# SparkFun_Qwiic_Audio_Amp.net
KiCad netlist of a schematic drawn in EAGLE
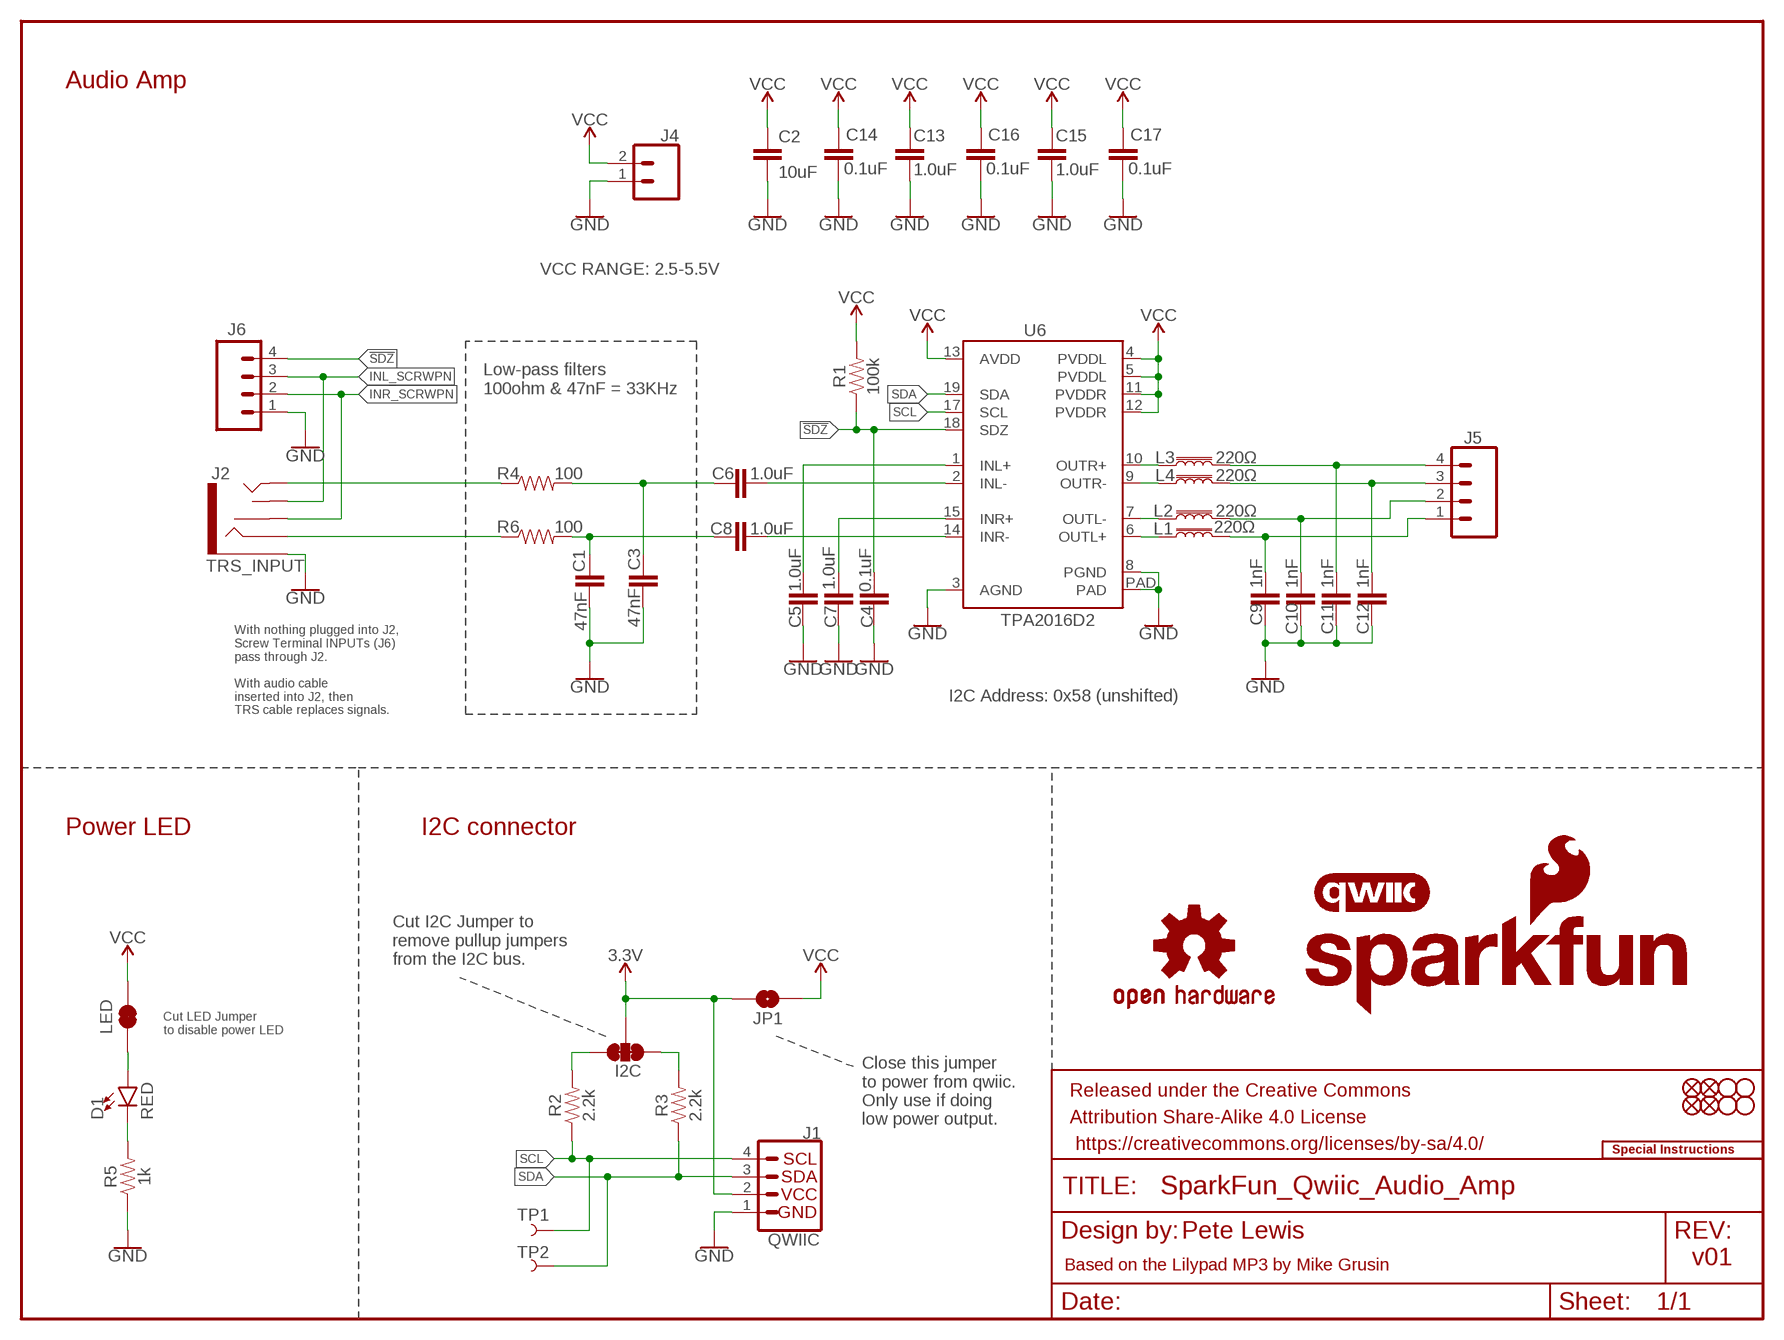
[diagram p0: schematic, sheet 1]

(export (version "E")
  (design (tool "Eeschema 10.0.6"))
  (components
    (comp (ref "C1")
      (value "47nF")
      (footprint "eagle-import:0402-TIGHT")
      (libsource (lib "eagle-import") (part "47NF-0402_TIGHT-25V-10%-X7R"))
    )
    (comp (ref "C2")
      (value "10uF")
      (footprint "eagle-import:0805")
      (libsource (lib "eagle-import") (part "10UF-0805-25V-10%"))
    )
    (comp (ref "C3")
      (value "47nF")
      (footprint "eagle-import:0402-TIGHT")
      (libsource (lib "eagle-import") (part "47NF-0402_TIGHT-25V-10%-X7R"))
    )
    (comp (ref "C4")
      (value "0.1uF")
      (footprint "eagle-import:0402-TIGHT")
      (libsource (lib "eagle-import") (part "0.1UF-0402T-16V-10%-X7R-WE"))
    )
    (comp (ref "C5")
      (value "1.0uF")
      (footprint "eagle-import:0402-TIGHT")
      (libsource (lib "eagle-import") (part "1.0UF-0402T-16V-10%"))
    )
    (comp (ref "C6")
      (value "1.0uF")
      (footprint "eagle-import:0402-TIGHT")
      (libsource (lib "eagle-import") (part "1.0UF-0402T-16V-10%"))
    )
    (comp (ref "C7")
      (value "1.0uF")
      (footprint "eagle-import:0402-TIGHT")
      (libsource (lib "eagle-import") (part "1.0UF-0402T-16V-10%"))
    )
    (comp (ref "C8")
      (value "1.0uF")
      (footprint "eagle-import:0402-TIGHT")
      (libsource (lib "eagle-import") (part "1.0UF-0402T-16V-10%"))
    )
    (comp (ref "C9")
      (value "1nF")
      (footprint "eagle-import:0402")
      (libsource (lib "eagle-import") (part "1.0NF/1000PF-0402-25V-10%-X7R"))
    )
    (comp (ref "C10")
      (value "1nF")
      (footprint "eagle-import:0402")
      (libsource (lib "eagle-import") (part "1.0NF/1000PF-0402-25V-10%-X7R"))
    )
    (comp (ref "C11")
      (value "1nF")
      (footprint "eagle-import:0402")
      (libsource (lib "eagle-import") (part "1.0NF/1000PF-0402-25V-10%-X7R"))
    )
    (comp (ref "C12")
      (value "1nF")
      (footprint "eagle-import:0402")
      (libsource (lib "eagle-import") (part "1.0NF/1000PF-0402-25V-10%-X7R"))
    )
    (comp (ref "C13")
      (value "1.0uF")
      (footprint "eagle-import:0402-TIGHT")
      (libsource (lib "eagle-import") (part "1.0UF-0402T-16V-10%"))
    )
    (comp (ref "C14")
      (value "0.1uF")
      (footprint "eagle-import:0402-TIGHT")
      (libsource (lib "eagle-import") (part "0.1UF-0402T-16V-10%-X7R-WE"))
    )
    (comp (ref "C15")
      (value "1.0uF")
      (footprint "eagle-import:0402-TIGHT")
      (libsource (lib "eagle-import") (part "1.0UF-0402T-16V-10%"))
    )
    (comp (ref "C16")
      (value "0.1uF")
      (footprint "eagle-import:0402-TIGHT")
      (libsource (lib "eagle-import") (part "0.1UF-0402T-16V-10%-X7R-WE"))
    )
    (comp (ref "C17")
      (value "0.1uF")
      (footprint "eagle-import:0402-TIGHT")
      (libsource (lib "eagle-import") (part "0.1UF-0402T-16V-10%-X7R-WE"))
    )
    (comp (ref "D1")
      (value "RED")
      (footprint "eagle-import:LED-0603")
      (libsource (lib "eagle-import") (part "LED-RED0603"))
    )
    (comp (ref "FD1")
      (value "FIDUCIAL1X2")
      (footprint "eagle-import:FIDUCIAL-1X2")
      (libsource (lib "eagle-import") (part "FIDUCIAL1X2"))
    )
    (comp (ref "FD2")
      (value "FIDUCIAL1X2")
      (footprint "eagle-import:FIDUCIAL-1X2")
      (libsource (lib "eagle-import") (part "FIDUCIAL1X2"))
    )
    (comp (ref "FD3")
      (value "FIDUCIAL1X2")
      (footprint "eagle-import:FIDUCIAL-1X2")
      (libsource (lib "eagle-import") (part "FIDUCIAL1X2"))
    )
    (comp (ref "FD4")
      (value "FIDUCIAL1X2")
      (footprint "eagle-import:FIDUCIAL-1X2")
      (libsource (lib "eagle-import") (part "FIDUCIAL1X2"))
    )
    (comp (ref "FRAME2")
      (value "FRAME-LETTER")
      (footprint "eagle-import:CREATIVE_COMMONS")
      (libsource (lib "eagle-import") (part "FRAME-LETTER"))
    )
    (comp (ref "H1")
      (value "STAND-OFFTIGHT")
      (footprint "eagle-import:STAND-OFF-TIGHT")
      (libsource (lib "eagle-import") (part "STAND-OFFTIGHT"))
    )
    (comp (ref "H2")
      (value "STAND-OFFTIGHT")
      (footprint "eagle-import:STAND-OFF-TIGHT")
      (libsource (lib "eagle-import") (part "STAND-OFFTIGHT"))
    )
    (comp (ref "H3")
      (value "STAND-OFFTIGHT")
      (footprint "eagle-import:STAND-OFF-TIGHT")
      (libsource (lib "eagle-import") (part "STAND-OFFTIGHT"))
    )
    (comp (ref "H4")
      (value "STAND-OFFTIGHT")
      (footprint "eagle-import:STAND-OFF-TIGHT")
      (libsource (lib "eagle-import") (part "STAND-OFFTIGHT"))
    )
    (comp (ref "I2C")
      (value "JUMPER-SMT_3_2-NC_TRACE_SILK")
      (footprint "eagle-import:SMT-JUMPER_3_2-NC_TRACE_SILK")
      (libsource (lib "eagle-import") (part "JUMPER-SMT_3_2-NC_TRACE_SILK"))
    )
    (comp (ref "J1")
      (value "QWIIC")
      (footprint "eagle-import:JST04_1MM_RA")
      (libsource (lib "eagle-import") (part "QWIIC_CONNECTORJS-1MM"))
    )
    (comp (ref "J2")
      (value "TRS_INPUT")
      (footprint "eagle-import:AUDIO-JACK-3.5MM-SMD")
      (libsource (lib "eagle-import") (part "AUDIO_JACK_3.5MM_SMD"))
    )
    (comp (ref "J4")
      (value "CONN_023.5MM")
      (footprint "eagle-import:SCREWTERMINAL-3.5MM-2")
      (libsource (lib "eagle-import") (part "CONN_023.5MM"))
    )
    (comp (ref "J5")
      (value "CONN_04SCREW")
      (footprint "eagle-import:SCREWTERMINAL-3.5MM-4")
      (libsource (lib "eagle-import") (part "CONN_04SCREW"))
    )
    (comp (ref "J6")
      (value "SCREW")
      (footprint "eagle-import:SCREWTERMINAL-3.5MM-4")
      (libsource (lib "eagle-import") (part "CONN_04SCREW"))
    )
    (comp (ref "JP1")
      (value "JP1")
      (footprint "eagle-import:SMT-JUMPER_2_NO_SILK")
      (libsource (lib "eagle-import") (part "JUMPER-SMT_2_NO_SILK"))
    )
    (comp (ref "L1")
      (value "220Ω")
      (footprint "eagle-import:0805")
      (libsource (lib "eagle-import") (part "FERRITE_BEAD-0805-220Ω-100MHZ-2A"))
    )
    (comp (ref "L2")
      (value "220Ω")
      (footprint "eagle-import:0805")
      (libsource (lib "eagle-import") (part "FERRITE_BEAD-0805-220Ω-100MHZ-2A"))
    )
    (comp (ref "L3")
      (value "220Ω")
      (footprint "eagle-import:0805")
      (libsource (lib "eagle-import") (part "FERRITE_BEAD-0805-220Ω-100MHZ-2A"))
    )
    (comp (ref "L4")
      (value "220Ω")
      (footprint "eagle-import:0805")
      (libsource (lib "eagle-import") (part "FERRITE_BEAD-0805-220Ω-100MHZ-2A"))
    )
    (comp (ref "LED")
      (value "JUMPER-SMT_2_NC_TRACE_SILK")
      (footprint "eagle-import:SMT-JUMPER_2_NC_TRACE_SILK")
      (libsource (lib "eagle-import") (part "JUMPER-SMT_2_NC_TRACE_SILK"))
    )
    (comp (ref "LOGO2")
      (value "SFE_LOGO_NAME_FLAME.1_INCH")
      (footprint "eagle-import:SFE_LOGO_NAME_FLAME_.1")
      (libsource (lib "eagle-import") (part "SFE_LOGO_NAME_FLAME.1_INCH"))
    )
    (comp (ref "LOGO3")
      (value "QWIIC_LOGO_4MM")
      (footprint "eagle-import:QWIIC_4MM")
      (libsource (lib "eagle-import") (part "QWIIC_LOGO_4MM"))
    )
    (comp (ref "LOGO4")
      (value "OSHW-LOGOS")
      (footprint "eagle-import:OSHW-LOGO-S")
      (libsource (lib "eagle-import") (part "OSHW-LOGOS"))
    )
    (comp (ref "LOGO5")
      (value "SFE_LOGO_FLAME.1_INCH")
      (footprint "eagle-import:SFE_LOGO_FLAME_.1")
      (libsource (lib "eagle-import") (part "SFE_LOGO_FLAME.1_INCH"))
    )
    (comp (ref "LOGO6")
      (value "SPECIAL_INSTRUCTIONS-ORDERING")
      (footprint "eagle-import:ORDERING_INSTRUCTIONS")
      (libsource (lib "eagle-import") (part "SPECIAL_INSTRUCTIONS-ORDERING"))
    )
    (comp (ref "R1")
      (value "100k")
      (footprint "eagle-import:0402-TIGHT")
      (libsource (lib "eagle-import") (part "100KOHM-0402T-1/16W-1%"))
    )
    (comp (ref "R2")
      (value "2.2k")
      (footprint "eagle-import:0402-TIGHT")
      (libsource (lib "eagle-import") (part "2.2KOHM-0402T-1/16W-1%"))
    )
    (comp (ref "R3")
      (value "2.2k")
      (footprint "eagle-import:0402-TIGHT")
      (libsource (lib "eagle-import") (part "2.2KOHM-0402T-1/16W-1%"))
    )
    (comp (ref "R4")
      (value "100")
      (footprint "eagle-import:0402-TIGHT")
      (libsource (lib "eagle-import") (part "100OHM-0402-TIGHT-1/16W-1%"))
    )
    (comp (ref "R5")
      (value "1k")
      (footprint "eagle-import:0402-TIGHT")
      (libsource (lib "eagle-import") (part "1KOHM-0402T-1/16W-1%"))
    )
    (comp (ref "R6")
      (value "100")
      (footprint "eagle-import:0402-TIGHT")
      (libsource (lib "eagle-import") (part "100OHM-0402-TIGHT-1/16W-1%"))
    )
    (comp (ref "TP1")
      (value "TEST-POINTTP_15TH_THRU")
      (footprint "eagle-import:TP_15TH")
      (libsource (lib "eagle-import") (part "TEST-POINTTP_15TH_THRU"))
    )
    (comp (ref "TP2")
      (value "TEST-POINTTP_15TH_THRU")
      (footprint "eagle-import:TP_15TH")
      (libsource (lib "eagle-import") (part "TEST-POINTTP_15TH_THRU"))
    )
    (comp (ref "U6")
      (value "TPA2016D2")
      (footprint "eagle-import:QFN-20-0.5MM")
      (libsource (lib "eagle-import") (part "TPA2016D2RTJ"))
    )
  )
  (nets
    (net (code "1") (name "/~{SDZ}") (class "Default")
      (node (ref "C4") (pin "1") (pinfunction "1_1") (pintype "passive"))
      (node (ref "J6") (pin "4") (pinfunction "4_4") (pintype "passive"))
      (node (ref "R1") (pin "1") (pinfunction "1_1") (pintype "passive"))
      (node (ref "U6") (pin "18") (pinfunction "SDZ_18") (pintype "input"))
    )
    (net (code "2") (name "3.3V") (class "Default")
      (node (ref "I2C") (pin "2") (pinfunction "2_2") (pintype "passive"))
      (node (ref "J1") (pin "2") (pinfunction "2_2") (pintype "power_in"))
      (node (ref "JP1") (pin "1") (pinfunction "1_1") (pintype "passive"))
    )
    (net (code "3") (name "GND") (class "Default")
      (node (ref "C1") (pin "2") (pinfunction "2_2") (pintype "passive"))
      (node (ref "C10") (pin "2") (pinfunction "2_2") (pintype "passive"))
      (node (ref "C11") (pin "2") (pinfunction "2_2") (pintype "passive"))
      (node (ref "C12") (pin "2") (pinfunction "2_2") (pintype "passive"))
      (node (ref "C13") (pin "2") (pinfunction "2_2") (pintype "passive"))
      (node (ref "C14") (pin "2") (pinfunction "2_2") (pintype "passive"))
      (node (ref "C15") (pin "2") (pinfunction "2_2") (pintype "passive"))
      (node (ref "C16") (pin "2") (pinfunction "2_2") (pintype "passive"))
      (node (ref "C17") (pin "2") (pinfunction "2_2") (pintype "passive"))
      (node (ref "C2") (pin "2") (pinfunction "2_2") (pintype "passive"))
      (node (ref "C3") (pin "2") (pinfunction "2_2") (pintype "passive"))
      (node (ref "C4") (pin "2") (pinfunction "2_2") (pintype "passive"))
      (node (ref "C5") (pin "1") (pinfunction "1_1") (pintype "passive"))
      (node (ref "C7") (pin "1") (pinfunction "1_1") (pintype "passive"))
      (node (ref "C9") (pin "2") (pinfunction "2_2") (pintype "passive"))
      (node (ref "J1") (pin "1") (pinfunction "1_1") (pintype "power_in"))
      (node (ref "J2") (pin "SLEEVE") (pinfunction "SLEEVE_SLEEVE") (pintype "bidirectional"))
      (node (ref "J4") (pin "1") (pinfunction "1_1") (pintype "passive"))
      (node (ref "J6") (pin "1") (pinfunction "1_1") (pintype "passive"))
      (node (ref "R5") (pin "1") (pinfunction "1_1") (pintype "passive"))
      (node (ref "U6") (pin "3") (pinfunction "AGND_3") (pintype "power_in"))
      (node (ref "U6") (pin "8") (pinfunction "PGND_8") (pintype "power_in"))
      (node (ref "U6") (pin "PAD") (pinfunction "PAD_PAD") (pintype "power_in"))
    )
    (net (code "4") (name "INL_SCRWPN") (class "Default")
      (node (ref "J2") (pin "TSH") (pinfunction "TSH_TSH") (pintype "bidirectional"))
      (node (ref "J6") (pin "3") (pinfunction "3_3") (pintype "passive"))
    )
    (net (code "5") (name "INR_SCRWPN") (class "Default")
      (node (ref "J2") (pin "RSH") (pinfunction "RSH_RSH") (pintype "bidirectional"))
      (node (ref "J6") (pin "2") (pinfunction "2_2") (pintype "passive"))
    )
    (net (code "6") (name "Net-(C1-Pad1)") (class "Default")
      (node (ref "C1") (pin "1") (pinfunction "1_1") (pintype "passive"))
      (node (ref "C8") (pin "1") (pinfunction "1_1") (pintype "passive"))
      (node (ref "R6") (pin "2") (pinfunction "2_2") (pintype "passive"))
    )
    (net (code "7") (name "Net-(C3-Pad1)") (class "Default")
      (node (ref "C3") (pin "1") (pinfunction "1_1") (pintype "passive"))
      (node (ref "C6") (pin "1") (pinfunction "1_1") (pintype "passive"))
      (node (ref "R4") (pin "2") (pinfunction "2_2") (pintype "passive"))
    )
    (net (code "8") (name "Net-(C9-Pad1)") (class "Default")
      (node (ref "C9") (pin "1") (pinfunction "1_1") (pintype "passive"))
      (node (ref "J5") (pin "1") (pinfunction "1_1") (pintype "passive"))
      (node (ref "L1") (pin "2") (pinfunction "2_2") (pintype "passive"))
    )
    (net (code "9") (name "Net-(C10-Pad1)") (class "Default")
      (node (ref "C10") (pin "1") (pinfunction "1_1") (pintype "passive"))
      (node (ref "J5") (pin "2") (pinfunction "2_2") (pintype "passive"))
      (node (ref "L2") (pin "2") (pinfunction "2_2") (pintype "passive"))
    )
    (net (code "10") (name "Net-(C11-Pad1)") (class "Default")
      (node (ref "C11") (pin "1") (pinfunction "1_1") (pintype "passive"))
      (node (ref "J5") (pin "4") (pinfunction "4_4") (pintype "passive"))
      (node (ref "L3") (pin "2") (pinfunction "2_2") (pintype "passive"))
    )
    (net (code "11") (name "Net-(C12-Pad1)") (class "Default")
      (node (ref "C12") (pin "1") (pinfunction "1_1") (pintype "passive"))
      (node (ref "J5") (pin "3") (pinfunction "3_3") (pintype "passive"))
      (node (ref "L4") (pin "2") (pinfunction "2_2") (pintype "passive"))
    )
    (net (code "12") (name "Net-(D1-PadA)") (class "Default")
      (node (ref "D1") (pin "A") (pinfunction "A_A") (pintype "passive"))
      (node (ref "LED") (pin "1") (pinfunction "1_1") (pintype "passive"))
    )
    (net (code "13") (name "Net-(D1-PadC)") (class "Default")
      (node (ref "D1") (pin "C") (pinfunction "C_C") (pintype "passive"))
      (node (ref "R5") (pin "2") (pinfunction "2_2") (pintype "passive"))
    )
    (net (code "14") (name "Net-(I2C-Pad1)") (class "Default")
      (node (ref "I2C") (pin "1") (pinfunction "1_1") (pintype "passive"))
      (node (ref "R3") (pin "2") (pinfunction "2_2") (pintype "passive"))
    )
    (net (code "15") (name "Net-(I2C-Pad3)") (class "Default")
      (node (ref "I2C") (pin "3") (pinfunction "3_3") (pintype "passive"))
      (node (ref "R2") (pin "2") (pinfunction "2_2") (pintype "passive"))
    )
    (net (code "16") (name "Net-(J2-PadRING)") (class "Default")
      (node (ref "J2") (pin "RING") (pinfunction "RING_RING") (pintype "bidirectional"))
      (node (ref "R6") (pin "1") (pinfunction "1_1") (pintype "passive"))
    )
    (net (code "17") (name "Net-(J2-PadTIP)") (class "Default")
      (node (ref "J2") (pin "TIP") (pinfunction "TIP_TIP") (pintype "bidirectional"))
      (node (ref "R4") (pin "1") (pinfunction "1_1") (pintype "passive"))
    )
    (net (code "18") (name "Net-(U6-INL+)") (class "Default")
      (node (ref "C5") (pin "2") (pinfunction "2_2") (pintype "passive"))
      (node (ref "U6") (pin "1") (pinfunction "INL+_1") (pintype "input"))
    )
    (net (code "19") (name "Net-(U6-INL-)") (class "Default")
      (node (ref "C6") (pin "2") (pinfunction "2_2") (pintype "passive"))
      (node (ref "U6") (pin "2") (pinfunction "INL-_2") (pintype "input"))
    )
    (net (code "20") (name "Net-(U6-INR+)") (class "Default")
      (node (ref "C7") (pin "2") (pinfunction "2_2") (pintype "passive"))
      (node (ref "U6") (pin "15") (pinfunction "INR+_15") (pintype "input"))
    )
    (net (code "21") (name "Net-(U6-INR-)") (class "Default")
      (node (ref "C8") (pin "2") (pinfunction "2_2") (pintype "passive"))
      (node (ref "U6") (pin "14") (pinfunction "INR-_14") (pintype "input"))
    )
    (net (code "22") (name "Net-(U6-OUTL+)") (class "Default")
      (node (ref "L1") (pin "1") (pinfunction "1_1") (pintype "passive"))
      (node (ref "U6") (pin "6") (pinfunction "OUTL+_6") (pintype "output"))
    )
    (net (code "23") (name "Net-(U6-OUTL-)") (class "Default")
      (node (ref "L2") (pin "1") (pinfunction "1_1") (pintype "passive"))
      (node (ref "U6") (pin "7") (pinfunction "OUTL-_7") (pintype "output"))
    )
    (net (code "24") (name "Net-(U6-OUTR+)") (class "Default")
      (node (ref "L3") (pin "1") (pinfunction "1_1") (pintype "passive"))
      (node (ref "U6") (pin "10") (pinfunction "OUTR+_10") (pintype "output"))
    )
    (net (code "25") (name "Net-(U6-OUTR-)") (class "Default")
      (node (ref "L4") (pin "1") (pinfunction "1_1") (pintype "passive"))
      (node (ref "U6") (pin "9") (pinfunction "OUTR-_9") (pintype "output"))
    )
    (net (code "26") (name "SCL") (class "Default")
      (node (ref "J1") (pin "4") (pinfunction "4_4") (pintype "passive"))
      (node (ref "R2") (pin "1") (pinfunction "1_1") (pintype "passive"))
      (node (ref "TP1") (pin "1") (pinfunction "1_1") (pintype "bidirectional"))
      (node (ref "U6") (pin "17") (pinfunction "SCL_17") (pintype "bidirectional"))
    )
    (net (code "27") (name "SDA") (class "Default")
      (node (ref "J1") (pin "3") (pinfunction "3_3") (pintype "passive"))
      (node (ref "R3") (pin "1") (pinfunction "1_1") (pintype "passive"))
      (node (ref "TP2") (pin "1") (pinfunction "1_1") (pintype "bidirectional"))
      (node (ref "U6") (pin "19") (pinfunction "SDA_19") (pintype "bidirectional"))
    )
    (net (code "28") (name "VCC") (class "Default")
      (node (ref "C13") (pin "1") (pinfunction "1_1") (pintype "passive"))
      (node (ref "C14") (pin "1") (pinfunction "1_1") (pintype "passive"))
      (node (ref "C15") (pin "1") (pinfunction "1_1") (pintype "passive"))
      (node (ref "C16") (pin "1") (pinfunction "1_1") (pintype "passive"))
      (node (ref "C17") (pin "1") (pinfunction "1_1") (pintype "passive"))
      (node (ref "C2") (pin "1") (pinfunction "1_1") (pintype "passive"))
      (node (ref "J4") (pin "2") (pinfunction "2_2") (pintype "passive"))
      (node (ref "JP1") (pin "2") (pinfunction "2_2") (pintype "passive"))
      (node (ref "LED") (pin "2") (pinfunction "2_2") (pintype "passive"))
      (node (ref "R1") (pin "2") (pinfunction "2_2") (pintype "passive"))
      (node (ref "U6") (pin "11") (pinfunction "PVDDR_11") (pintype "power_in"))
      (node (ref "U6") (pin "12") (pinfunction "PVDDR_12") (pintype "power_in"))
      (node (ref "U6") (pin "13") (pinfunction "AVDD_13") (pintype "power_in"))
      (node (ref "U6") (pin "4") (pinfunction "PVDDL_4") (pintype "power_in"))
      (node (ref "U6") (pin "5") (pinfunction "PVDDL_5") (pintype "power_in"))
    )
  )
)
